# EsquematicoDevkit.net
KiCad netlist of a schematic drawn in Altium Designer
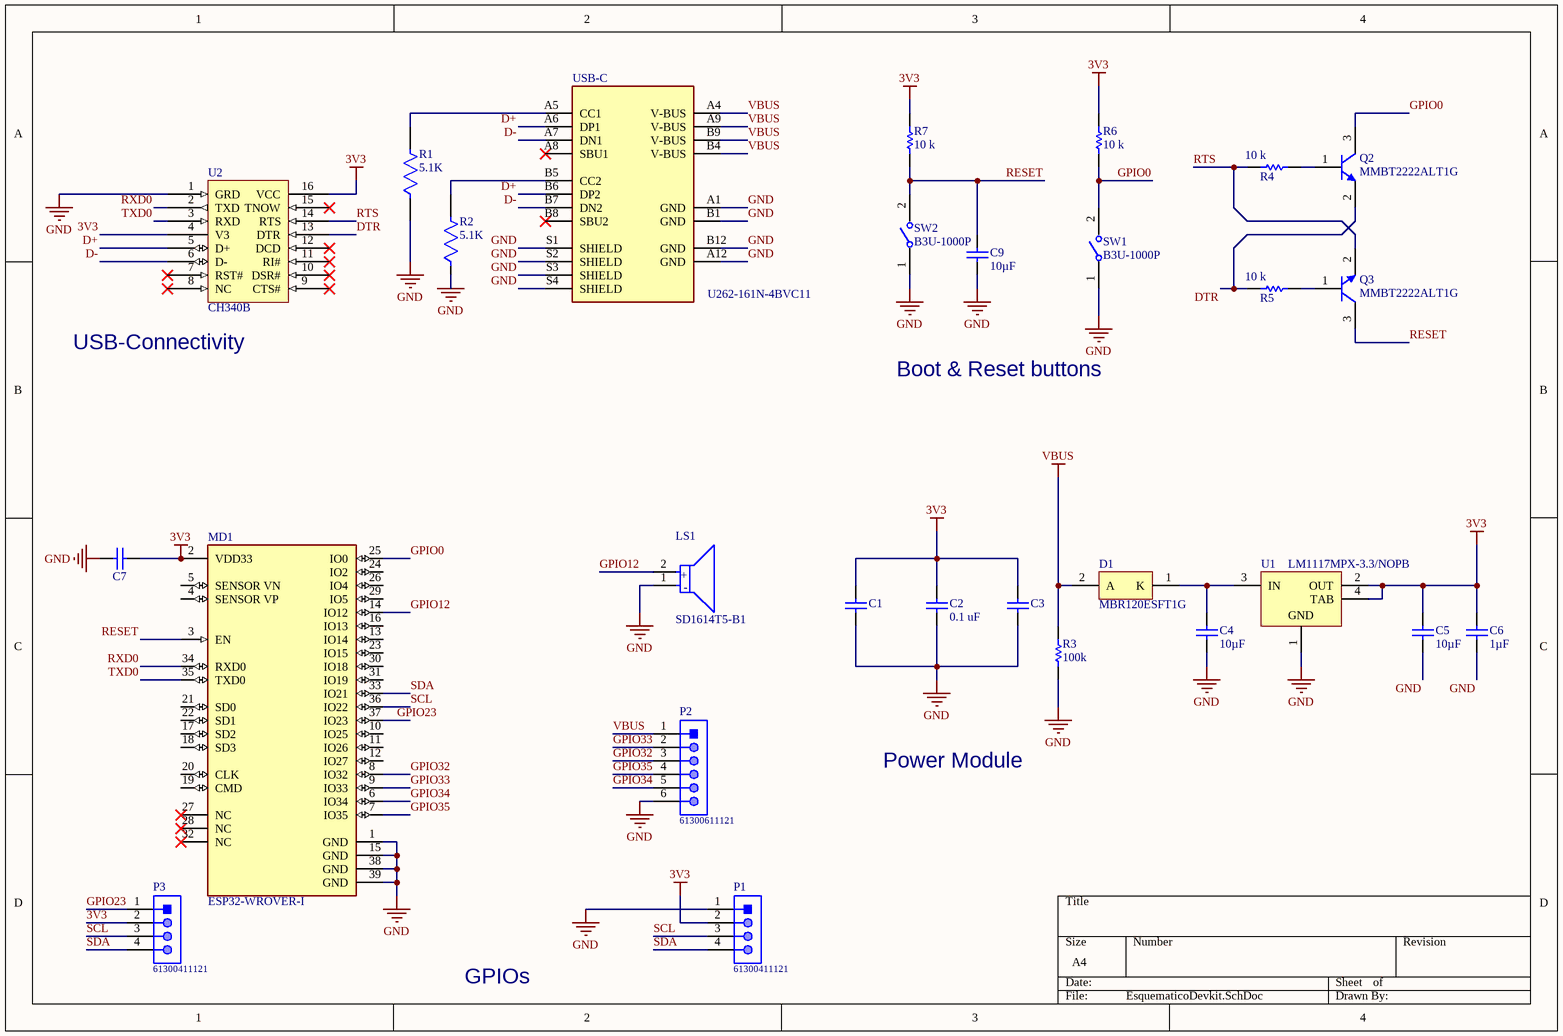
[diagram p0: EsquematicoDevkit.SchDoc]

(export (version "E")
  (design (tool "Eeschema 10.0.6"))
  (components
    (comp (ref "C1")
      (value "C0805C106K4PACTU")
      (footprint "CAPC2013X140X50ML20T25")
      (description "10µF ±10% 16V Ceramic Capacitor X5R 0805 (2012 Metric)")
      (fields (field (name "PART NUMBER") "CL21A106KOQNNNG"))
      (libsource (lib "Altium Content Vault") (part "CAP"))
    )
    (comp (ref "C2")
      (value "0.1 uF")
      (footprint "CAPC2013X94X50ML20T25")
      (description "Chip Capacitor, Ceramic, 0.1 uF, 10%, 50 V, 0805, RoHS, Tape and Reel")
      (fields (field (name "MANUFACTURER") "AVX"))
      (libsource (lib "Altium Content Vault") (part "CAP-NP-2"))
    )
    (comp (ref "C3")
      (value "C0805C106K4PACTU")
      (footprint "CAPC2013X140X50ML20T25")
      (description "10µF ±10% 16V Ceramic Capacitor X5R 0805 (2012 Metric)")
      (fields (field (name "PART NUMBER") "CL21A106KOQNNNG"))
      (libsource (lib "Altium Content Vault") (part "CAP"))
    )
    (comp (ref "C4")
      (value "10µF")
      (footprint "CAPC2013X140X50ML20T25")
      (description "10µF ±10% 16V Ceramic Capacitor X5R 0805 (2012 Metric)")
      (fields (field (name "PART NUMBER") "CL21A106KOQNNNG"))
      (libsource (lib "Altium Content Vault") (part "CAP"))
    )
    (comp (ref "C5")
      (value "10µF")
      (footprint "CAPC2013X140X50ML20T25")
      (description "10µF ±10% 16V Ceramic Capacitor X5R 0805 (2012 Metric)")
      (fields (field (name "PART NUMBER") "CL21A106KOQNNNG"))
      (libsource (lib "Altium Content Vault") (part "CAP"))
    )
    (comp (ref "C6")
      (value "1µF")
      (footprint "CAPC2013X145X50ML20T25")
      (description "1µF ±10% 16V Ceramic Capacitor X7R 0805 (2012 Metric)")
      (fields (field (name "MANUFACTURER") "Kemet") (field (name "PART NUMBER") "C0805C105K4RAC7800"))
      (libsource (lib "Altium Content Vault") (part "CAP"))
    )
    (comp (ref "C7")
      (value "08055C104KAT2A")
      (footprint "CAPC2013X94X50ML20T25")
      (description "Chip Capacitor, Ceramic, 0.1 uF, 10%, 50 V, 0805, RoHS, Tape and Reel")
      (fields (field (name "MANUFACTURER") "AVX"))
      (libsource (lib "Altium Content Vault") (part "CAP-NP-2"))
    )
    (comp (ref "C9")
      (value "10µF")
      (footprint "CAPC2013X145X50ML20T25")
      (description "10µF ±10% 16V Ceramic Capacitor X7R 0805 (2012 Metric)")
      (fields (field (name "MANUFACTURER") "Kemet") (field (name "PART NUMBER") "C0805C105K4RAC7800"))
      (libsource (lib "Altium Content Vault") (part "CAP"))
    )
    (comp (ref "D1")
      (value "MBR120ESFT1G")
      (footprint "ONSC-SOD-123FL-2-498_V")
      (description "Schottky Power Rectifier, 2-Pin SOD-123, Pb-Free, Tape and Reel")
      (fields (field (name "MANUFACTURER") "On Semiconductor"))
      (libsource (lib "Altium Content Vault") (part "ONSC-D-K1A2-2_A"))
    )
    (comp (ref "LS1")
      (value "SD1614T5-B1")
      (footprint "FP-SD1614T5-B1-MFG")
      (description "AUDIO MAGNETIC XDCR 3-6V TH")
      (libsource (lib "Altium Content Vault") (part "f7ec632b6fea80cbef86dc3340f200c"))
    )
    (comp (ref "MD1")
      (value "ESP32-WROVER-I")
      (footprint "FP-ESP32-WROVER-I-MFG")
      (description "SMD MODULE, ESP32-D0WDQ6, 32MBIT")
      (fields
        (field (name "MANUFACTURER") "Espressif")
        (field (name "OCTOPART") "https://octopart.com/esp32-wrover-i-espressif+systems-89171349")
      )
      (libsource (lib "Altium Content Vault") (part "cbbb37af8bcfe61dfd46ac9418f0340"))
    )
    (comp (ref "P1")
      (value "61300411121")
      (footprint "61300411121")
      (description "THT Vertical Pin Header WR-PHD, Pitch 2.54 mm, Single Row, 4 pins")
      (fields (field (name "MANUFACTURER") "Wurth Elektronik") (field (name "PUBLISHER") "WurthElektronik"))
      (libsource (lib "Altium Content Vault") (part "WE-CN-1P-M-R4"))
    )
    (comp (ref "P2")
      (value "61300611121")
      (footprint "61300611121")
      (description "THT Vertical Pin Header WR-PHD, Pitch 2.54 mm, Single Row, 6 pins")
      (fields (field (name "MANUFACTURER") "Wurth Elektronik") (field (name "PUBLISHER") "WurthElektronik"))
      (libsource (lib "Altium Content Vault") (part "WE-CN-1P-M-R6"))
    )
    (comp (ref "P3")
      (value "61300411121")
      (footprint "61300411121")
      (description "THT Vertical Pin Header WR-PHD, Pitch 2.54 mm, Single Row, 4 pins")
      (fields (field (name "MANUFACTURER") "Wurth Elektronik") (field (name "PUBLISHER") "WurthElektronik"))
      (libsource (lib "Altium Content Vault") (part "WE-CN-1P-M-R4"))
    )
    (comp (ref "Q2")
      (value "MMBT2222ALT1G")
      (footprint "ONSC-SOT-23-3-318-08_V")
      (description "General Purpose Transistor, NPN Silicon, 3-Pin SOT-23, Pb-Free, Tape and Reel")
      (fields (field (name "MANUFACTURER") "On Semiconductor"))
      (libsource (lib "Altium Content Vault") (part "ONSC-NPN-B1E2C3-3"))
    )
    (comp (ref "Q3")
      (value "MMBT2222ALT1G")
      (footprint "ONSC-SOT-23-3-318-08_V")
      (description "General Purpose Transistor, NPN Silicon, 3-Pin SOT-23, Pb-Free, Tape and Reel")
      (fields (field (name "MANUFACTURER") "On Semiconductor"))
      (libsource (lib "Altium Content Vault") (part "ONSC-NPN-B1E2C3-3"))
    )
    (comp (ref "R1")
      (value "5.1K")
      (footprint "FP-CRCW0805-e3-MFG")
      (description "RES Thick Film, 5.1kΩ, 1%, 0.125W, 100ppm/°C, 0805")
      (fields (field (name "TOLERANCE") "1%"))
      (libsource (lib "Altium Content Vault") (part "1029c3af85768c4190bb7ad29bc67b5"))
    )
    (comp (ref "R2")
      (value "5.1K")
      (footprint "FP-CRCW0805-e3-MFG")
      (description "RES Thick Film, 5.1kΩ, 1%, 0.125W, 100ppm/°C, 0805")
      (fields (field (name "TOLERANCE") "1%"))
      (libsource (lib "Altium Content Vault") (part "1029c3af85768c4190bb7ad29bc67b5"))
    )
    (comp (ref "R3")
      (value "100k")
      (footprint "RESC2013X60X40ML20T25")
      (description "100 kOhms ±0.1% 0.125W, 1/8W Chip Resistor 0805 (2012 Metric) Automotive AEC-Q200 Thin Film")
      (fields (field (name "PART NUMBER") "ERA6AEB104V") (field (name "MANUFACTURER") "Panasonic"))
      (libsource (lib "Altium Content Vault") (part "RES"))
    )
    (comp (ref "R4")
      (value "10 k")
      (footprint "RESC2013X60X30ML20T20")
      (fields (field (name "PART NUMBER") "RK73B2ATTD103J") (field (name "MANUFACTURER") "KOA Speer"))
      (libsource (lib "Altium Content Vault") (part "RES"))
    )
    (comp (ref "R5")
      (value "10 k")
      (footprint "RESC2013X60X30ML20T20")
      (fields (field (name "PART NUMBER") "RK73B2ATTD103J") (field (name "MANUFACTURER") "KOA Speer"))
      (libsource (lib "Altium Content Vault") (part "RES"))
    )
    (comp (ref "R6")
      (value "10 k")
      (footprint "RESC2013X60X30ML20T20")
      (fields (field (name "PART NUMBER") "RK73B2ATTD103J") (field (name "MANUFACTURER") "KOA Speer"))
      (libsource (lib "Altium Content Vault") (part "RES"))
    )
    (comp (ref "R7")
      (value "10 k")
      (footprint "RESC2013X60X30ML20T20")
      (fields (field (name "PART NUMBER") "RK73B2ATTD103J") (field (name "MANUFACTURER") "KOA Speer"))
      (libsource (lib "Altium Content Vault") (part "RES"))
    )
    (comp (ref "SW1")
      (value "B3U-1000P")
      (footprint "FP-B3U-1000P-MFG")
      (description "SWITCH TACTILE SPST-NO 0.05A 12V")
      (libsource (lib "Altium Content Vault") (part "ae622034201233ca1abcedc05908f33"))
    )
    (comp (ref "SW2")
      (value "B3U-1000P")
      (footprint "FP-B3U-1000P-MFG")
      (description "SWITCH TACTILE SPST-NO 0.05A 12V")
      (libsource (lib "Altium Content Vault") (part "ae622034201233ca1abcedc05908f33"))
    )
    (comp (ref "U1")
      (value "LM1117MPX-3.3/NOPB")
      (footprint "DCY0004A_M")
      (description "800mA Low-Dropout Linear Regulator, 4-pin SOT-223, Pb-Free")
      (fields (field (name "MANUFACTURER") "Texas Instruments"))
      (libsource (lib "Altium Content Vault") (part "PM-REG-LM1086-SOT4"))
    )
    (comp (ref "U2")
      (value "CH340B")
      (footprint "CH340B")
      (description "- USB 2.0 Transceiver 2Mbps SOP-16_150mil USB ICs ROHS")
      (libsource (lib "Schlib1") (part "CH340B"))
    )
    (comp (ref "USB-C")
      (value "U262-161N-4BVC11")
      (footprint "U262-161N-4BVC11")
      (description "USB - Type C Female 16 SMT USB Connectors RoHS")
      (libsource (lib "Schlib1") (part "U262-161N-4BVC11"))
    )
  )
  (nets
    (net (code "1") (name "/D+") (class "Default")
      (node (ref "U2") (pin "5") (pinfunction "D+_5") (pintype "bidirectional"))
      (node (ref "USB-C") (pin "A6") (pinfunction "DP1_A6") (pintype "power_in"))
      (node (ref "USB-C") (pin "B6") (pinfunction "DP2_B6") (pintype "power_in"))
    )
    (net (code "2") (name "/D-") (class "Default")
      (node (ref "U2") (pin "6") (pinfunction "D-_6") (pintype "bidirectional"))
      (node (ref "USB-C") (pin "A7") (pinfunction "DN1_A7") (pintype "power_in"))
      (node (ref "USB-C") (pin "B7") (pinfunction "DN2_B7") (pintype "power_in"))
    )
    (net (code "3") (name "/DTR") (class "Default")
      (node (ref "Q2") (pin "2") (pinfunction "E_2") (pintype "passive"))
      (node (ref "R5") (pin "2") (pinfunction "2_2") (pintype "passive"))
      (node (ref "U2") (pin "13") (pinfunction "DTR_13") (pintype "input"))
    )
    (net (code "4") (name "/GPIO0") (class "Default")
      (node (ref "MD1") (pin "25") (pinfunction "IO0_25") (pintype "bidirectional"))
      (node (ref "Q2") (pin "3") (pinfunction "C_3") (pintype "passive"))
      (node (ref "R6") (pin "1") (pinfunction "1_1") (pintype "passive"))
      (node (ref "SW1") (pin "2") (pinfunction "2_2") (pintype "passive"))
    )
    (net (code "5") (name "/GPIO12") (class "Default")
      (node (ref "LS1") (pin "2") (pinfunction "A_2") (pintype "passive"))
      (node (ref "MD1") (pin "14") (pinfunction "IO12_14") (pintype "bidirectional"))
    )
    (net (code "6") (name "/GPIO23") (class "Default")
      (node (ref "MD1") (pin "37") (pinfunction "IO23_37") (pintype "bidirectional"))
      (node (ref "P3") (pin "1") (pinfunction "1_1") (pintype "passive"))
    )
    (net (code "7") (name "/GPIO32") (class "Default")
      (node (ref "MD1") (pin "8") (pinfunction "IO32_8") (pintype "bidirectional"))
      (node (ref "P2") (pin "3") (pinfunction "3_3") (pintype "passive"))
    )
    (net (code "8") (name "/GPIO33") (class "Default")
      (node (ref "MD1") (pin "9") (pinfunction "IO33_9") (pintype "bidirectional"))
      (node (ref "P2") (pin "2") (pinfunction "2_2") (pintype "passive"))
    )
    (net (code "9") (name "/GPIO34") (class "Default")
      (node (ref "MD1") (pin "6") (pinfunction "IO34_6") (pintype "bidirectional"))
      (node (ref "P2") (pin "5") (pinfunction "5_5") (pintype "passive"))
    )
    (net (code "10") (name "/GPIO35") (class "Default")
      (node (ref "MD1") (pin "7") (pinfunction "IO35_7") (pintype "bidirectional"))
      (node (ref "P2") (pin "4") (pinfunction "4_4") (pintype "passive"))
    )
    (net (code "11") (name "/RESET") (class "Default")
      (node (ref "C9") (pin "2") (pinfunction "2_2") (pintype "passive"))
      (node (ref "MD1") (pin "3") (pinfunction "EN_3") (pintype "input"))
      (node (ref "Q3") (pin "3") (pinfunction "C_3") (pintype "passive"))
      (node (ref "R7") (pin "1") (pinfunction "1_1") (pintype "passive"))
      (node (ref "SW2") (pin "2") (pinfunction "2_2") (pintype "passive"))
    )
    (net (code "12") (name "/RTS") (class "Default")
      (node (ref "Q3") (pin "2") (pinfunction "E_2") (pintype "passive"))
      (node (ref "R4") (pin "2") (pinfunction "2_2") (pintype "passive"))
      (node (ref "U2") (pin "14") (pinfunction "RTS_14") (pintype "input"))
    )
    (net (code "13") (name "/RXD0") (class "Default")
      (node (ref "MD1") (pin "34") (pinfunction "RXD0_34") (pintype "bidirectional"))
      (node (ref "U2") (pin "2") (pinfunction "TXD_2") (pintype "output"))
    )
    (net (code "14") (name "/SCL") (class "Default")
      (node (ref "MD1") (pin "36") (pinfunction "IO22_36") (pintype "bidirectional"))
      (node (ref "P1") (pin "3") (pinfunction "3_3") (pintype "passive"))
      (node (ref "P3") (pin "3") (pinfunction "3_3") (pintype "passive"))
    )
    (net (code "15") (name "/SDA") (class "Default")
      (node (ref "MD1") (pin "33") (pinfunction "IO21_33") (pintype "bidirectional"))
      (node (ref "P1") (pin "4") (pinfunction "4_4") (pintype "passive"))
      (node (ref "P3") (pin "4") (pinfunction "4_4") (pintype "passive"))
    )
    (net (code "16") (name "/TXD0") (class "Default")
      (node (ref "MD1") (pin "35") (pinfunction "TXD0_35") (pintype "bidirectional"))
      (node (ref "U2") (pin "3") (pinfunction "RXD_3") (pintype "input"))
    )
    (net (code "17") (name "3V3") (class "Default")
      (node (ref "C1") (pin "2") (pinfunction "2_2") (pintype "passive"))
      (node (ref "C2") (pin "2") (pinfunction "2_2") (pintype "passive"))
      (node (ref "C3") (pin "2") (pinfunction "2_2") (pintype "passive"))
      (node (ref "C5") (pin "2") (pinfunction "2_2") (pintype "passive"))
      (node (ref "C6") (pin "2") (pinfunction "2_2") (pintype "passive"))
      (node (ref "C7") (pin "2") (pinfunction "2_2") (pintype "passive"))
      (node (ref "MD1") (pin "2") (pinfunction "VDD33_2") (pintype "power_in"))
      (node (ref "P1") (pin "2") (pinfunction "2_2") (pintype "passive"))
      (node (ref "P3") (pin "2") (pinfunction "2_2") (pintype "passive"))
      (node (ref "R6") (pin "2") (pinfunction "2_2") (pintype "passive"))
      (node (ref "R7") (pin "2") (pinfunction "2_2") (pintype "passive"))
      (node (ref "U1") (pin "2") (pinfunction "OUT_2") (pintype "power_in"))
      (node (ref "U1") (pin "4") (pinfunction "TAB_4") (pintype "power_in"))
      (node (ref "U2") (pin "16") (pinfunction "VCC_16") (pintype "power_in"))
      (node (ref "U2") (pin "4") (pinfunction "V3_4") (pintype "power_in"))
    )
    (net (code "18") (name "GND") (class "Default")
      (node (ref "C1") (pin "1") (pinfunction "1_1") (pintype "passive"))
      (node (ref "C2") (pin "1") (pinfunction "1_1") (pintype "passive"))
      (node (ref "C3") (pin "1") (pinfunction "1_1") (pintype "passive"))
      (node (ref "C4") (pin "1") (pinfunction "1_1") (pintype "passive"))
      (node (ref "C5") (pin "1") (pinfunction "1_1") (pintype "passive"))
      (node (ref "C6") (pin "1") (pinfunction "1_1") (pintype "passive"))
      (node (ref "C7") (pin "1") (pinfunction "1_1") (pintype "passive"))
      (node (ref "C9") (pin "1") (pinfunction "1_1") (pintype "passive"))
      (node (ref "LS1") (pin "1") (pinfunction "C_1") (pintype "passive"))
      (node (ref "MD1") (pin "1") (pinfunction "GND_1") (pintype "power_in"))
      (node (ref "MD1") (pin "15") (pinfunction "GND_15") (pintype "power_in"))
      (node (ref "MD1") (pin "38") (pinfunction "GND_38") (pintype "power_in"))
      (node (ref "MD1") (pin "39") (pinfunction "GND_39") (pintype "power_in"))
      (node (ref "P1") (pin "1") (pinfunction "1_1") (pintype "passive"))
      (node (ref "P2") (pin "6") (pinfunction "6_6") (pintype "passive"))
      (node (ref "R1") (pin "1") (pinfunction "1_1") (pintype "passive"))
      (node (ref "R2") (pin "1") (pinfunction "1_1") (pintype "passive"))
      (node (ref "R3") (pin "1") (pinfunction "1_1") (pintype "passive"))
      (node (ref "SW1") (pin "1") (pinfunction "1_1") (pintype "passive"))
      (node (ref "SW2") (pin "1") (pinfunction "1_1") (pintype "passive"))
      (node (ref "U1") (pin "1") (pinfunction "GND_1") (pintype "power_in"))
      (node (ref "U2") (pin "1") (pinfunction "GRD_1") (pintype "input"))
      (node (ref "USB-C") (pin "A1") (pinfunction "GND_A1") (pintype "power_in"))
      (node (ref "USB-C") (pin "A12") (pinfunction "GND_A12") (pintype "power_in"))
      (node (ref "USB-C") (pin "B1") (pinfunction "GND_B1") (pintype "power_in"))
      (node (ref "USB-C") (pin "B12") (pinfunction "GND_B12") (pintype "power_in"))
      (node (ref "USB-C") (pin "S1") (pinfunction "SHIELD_S1") (pintype "passive"))
      (node (ref "USB-C") (pin "S2") (pinfunction "SHIELD_S2") (pintype "passive"))
      (node (ref "USB-C") (pin "S3") (pinfunction "SHIELD_S3") (pintype "passive"))
      (node (ref "USB-C") (pin "S4") (pinfunction "SHIELD_S4") (pintype "passive"))
    )
    (net (code "19") (name "Net-(D1-K)") (class "Default")
      (node (ref "C4") (pin "2") (pinfunction "2_2") (pintype "passive"))
      (node (ref "D1") (pin "1") (pinfunction "K_1") (pintype "passive"))
      (node (ref "U1") (pin "3") (pinfunction "IN_3") (pintype "power_in"))
    )
    (net (code "20") (name "Net-(Q2-B)") (class "Default")
      (node (ref "Q2") (pin "1") (pinfunction "B_1") (pintype "passive"))
      (node (ref "R4") (pin "1") (pinfunction "1_1") (pintype "passive"))
    )
    (net (code "21") (name "Net-(Q3-B)") (class "Default")
      (node (ref "Q3") (pin "1") (pinfunction "B_1") (pintype "passive"))
      (node (ref "R5") (pin "1") (pinfunction "1_1") (pintype "passive"))
    )
    (net (code "22") (name "Net-(USB-C-CC1)") (class "Default")
      (node (ref "R1") (pin "2") (pinfunction "2_2") (pintype "passive"))
      (node (ref "USB-C") (pin "A5") (pinfunction "CC1_A5") (pintype "power_in"))
    )
    (net (code "23") (name "Net-(USB-C-CC2)") (class "Default")
      (node (ref "R2") (pin "2") (pinfunction "2_2") (pintype "passive"))
      (node (ref "USB-C") (pin "B5") (pinfunction "CC2_B5") (pintype "power_in"))
    )
    (net (code "24") (name "VBUS") (class "Default")
      (node (ref "D1") (pin "2") (pinfunction "A_2") (pintype "passive"))
      (node (ref "P2") (pin "1") (pinfunction "1_1") (pintype "passive"))
      (node (ref "R3") (pin "2") (pinfunction "2_2") (pintype "passive"))
      (node (ref "USB-C") (pin "A4") (pinfunction "V-BUS_A4") (pintype "power_in"))
      (node (ref "USB-C") (pin "A9") (pinfunction "V-BUS_A9") (pintype "power_in"))
      (node (ref "USB-C") (pin "B4") (pinfunction "V-BUS_B4") (pintype "power_in"))
      (node (ref "USB-C") (pin "B9") (pinfunction "V-BUS_B9") (pintype "power_in"))
    )
    (net (code "25") (name "unconnected-(MD1-CLK-Pad20)") (class "Default")
      (node (ref "MD1") (pin "20") (pinfunction "CLK_20") (pintype "bidirectional"))
    )
    (net (code "26") (name "unconnected-(MD1-CMD-Pad19)") (class "Default")
      (node (ref "MD1") (pin "19") (pinfunction "CMD_19") (pintype "bidirectional"))
    )
    (net (code "27") (name "unconnected-(MD1-IO2-Pad24)") (class "Default")
      (node (ref "MD1") (pin "24") (pinfunction "IO2_24") (pintype "bidirectional"))
    )
    (net (code "28") (name "unconnected-(MD1-IO4-Pad26)") (class "Default")
      (node (ref "MD1") (pin "26") (pinfunction "IO4_26") (pintype "bidirectional"))
    )
    (net (code "29") (name "unconnected-(MD1-IO5-Pad29)") (class "Default")
      (node (ref "MD1") (pin "29") (pinfunction "IO5_29") (pintype "bidirectional"))
    )
    (net (code "30") (name "unconnected-(MD1-IO13-Pad16)") (class "Default")
      (node (ref "MD1") (pin "16") (pinfunction "IO13_16") (pintype "bidirectional"))
    )
    (net (code "31") (name "unconnected-(MD1-IO14-Pad13)") (class "Default")
      (node (ref "MD1") (pin "13") (pinfunction "IO14_13") (pintype "bidirectional"))
    )
    (net (code "32") (name "unconnected-(MD1-IO15-Pad23)") (class "Default")
      (node (ref "MD1") (pin "23") (pinfunction "IO15_23") (pintype "bidirectional"))
    )
    (net (code "33") (name "unconnected-(MD1-IO18-Pad30)") (class "Default")
      (node (ref "MD1") (pin "30") (pinfunction "IO18_30") (pintype "bidirectional"))
    )
    (net (code "34") (name "unconnected-(MD1-IO19-Pad31)") (class "Default")
      (node (ref "MD1") (pin "31") (pinfunction "IO19_31") (pintype "bidirectional"))
    )
    (net (code "35") (name "unconnected-(MD1-IO25-Pad10)") (class "Default")
      (node (ref "MD1") (pin "10") (pinfunction "IO25_10") (pintype "bidirectional"))
    )
    (net (code "36") (name "unconnected-(MD1-IO26-Pad11)") (class "Default")
      (node (ref "MD1") (pin "11") (pinfunction "IO26_11") (pintype "bidirectional"))
    )
    (net (code "37") (name "unconnected-(MD1-IO27-Pad12)") (class "Default")
      (node (ref "MD1") (pin "12") (pinfunction "IO27_12") (pintype "bidirectional"))
    )
    (net (code "38") (name "unconnected-(MD1-NC-Pad27)") (class "Default")
      (node (ref "MD1") (pin "27") (pinfunction "NC_27") (pintype "passive+no_connect"))
    )
    (net (code "39") (name "unconnected-(MD1-NC-Pad28)") (class "Default")
      (node (ref "MD1") (pin "28") (pinfunction "NC_28") (pintype "passive+no_connect"))
    )
    (net (code "40") (name "unconnected-(MD1-NC-Pad32)") (class "Default")
      (node (ref "MD1") (pin "32") (pinfunction "NC_32") (pintype "passive+no_connect"))
    )
    (net (code "41") (name "unconnected-(MD1-SD0-Pad21)") (class "Default")
      (node (ref "MD1") (pin "21") (pinfunction "SD0_21") (pintype "bidirectional"))
    )
    (net (code "42") (name "unconnected-(MD1-SD1-Pad22)") (class "Default")
      (node (ref "MD1") (pin "22") (pinfunction "SD1_22") (pintype "bidirectional"))
    )
    (net (code "43") (name "unconnected-(MD1-SD2-Pad17)") (class "Default")
      (node (ref "MD1") (pin "17") (pinfunction "SD2_17") (pintype "bidirectional"))
    )
    (net (code "44") (name "unconnected-(MD1-SD3-Pad18)") (class "Default")
      (node (ref "MD1") (pin "18") (pinfunction "SD3_18") (pintype "bidirectional"))
    )
    (net (code "45") (name "unconnected-(MD1-SENSOR_VN-Pad5)") (class "Default")
      (node (ref "MD1") (pin "5") (pinfunction "SENSOR_VN_5") (pintype "bidirectional"))
    )
    (net (code "46") (name "unconnected-(MD1-SENSOR_VP-Pad4)") (class "Default")
      (node (ref "MD1") (pin "4") (pinfunction "SENSOR_VP_4") (pintype "bidirectional"))
    )
    (net (code "47") (name "unconnected-(U2-CTS#-Pad9)") (class "Default")
      (node (ref "U2") (pin "9") (pinfunction "CTS#_9") (pintype "input+no_connect"))
    )
    (net (code "48") (name "unconnected-(U2-DCD-Pad12)") (class "Default")
      (node (ref "U2") (pin "12") (pinfunction "DCD_12") (pintype "input+no_connect"))
    )
    (net (code "49") (name "unconnected-(U2-DSR#-Pad10)") (class "Default")
      (node (ref "U2") (pin "10") (pinfunction "DSR#_10") (pintype "input+no_connect"))
    )
    (net (code "50") (name "unconnected-(U2-NC-Pad8)") (class "Default")
      (node (ref "U2") (pin "8") (pinfunction "NC_8") (pintype "input+no_connect"))
    )
    (net (code "51") (name "unconnected-(U2-RI#-Pad11)") (class "Default")
      (node (ref "U2") (pin "11") (pinfunction "RI#_11") (pintype "input+no_connect"))
    )
    (net (code "52") (name "unconnected-(U2-RST#-Pad7)") (class "Default")
      (node (ref "U2") (pin "7") (pinfunction "RST#_7") (pintype "input+no_connect"))
    )
    (net (code "53") (name "unconnected-(U2-TNOW-Pad15)") (class "Default")
      (node (ref "U2") (pin "15") (pinfunction "TNOW_15") (pintype "input+no_connect"))
    )
    (net (code "54") (name "unconnected-(USB-C-SBU1-PadA8)") (class "Default")
      (node (ref "USB-C") (pin "A8") (pinfunction "SBU1_A8") (pintype "power_in+no_connect"))
    )
    (net (code "55") (name "unconnected-(USB-C-SBU2-PadB8)") (class "Default")
      (node (ref "USB-C") (pin "B8") (pinfunction "SBU2_B8") (pintype "power_in+no_connect"))
    )
  )
)
